# PORT_SINGLE.net
KiCad netlist of a schematic drawn in Altium Designer
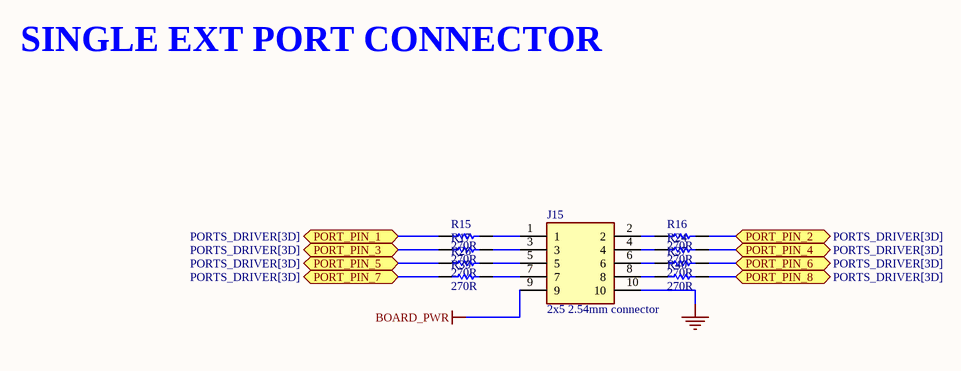
[diagram p0: PORT_SINGLE.SchDoc]

(export (version "E")
  (design (tool "Eeschema 10.0.6"))
  (components
    (comp (ref "J15")
      (value "2x5 2.54mm connector")
      (footprint "PcbLib1:SHDR10W64P254_2X5_2032X910X935P")
      (description "2x5position -  2.54x2.54mm connector")
      (fields (field (name "PARTNUMBER") "G821EU210AAL10Y"))
      (libsource (lib "Schlib1") (part "connector - 5x2 -  2.54x2.54mm"))
    )
    (comp (ref "R15")
      (value "270R")
      (footprint "RESC1005X40X25NL05T05")
      (description "Resistor - 0402 - 270R - 1% - 125mW")
      (fields (field (name "PARTNUMBER") "CRGP0402F270R"))
      (libsource (lib "Schlib1") (part "Resistor - 0402 -270R"))
    )
    (comp (ref "R16")
      (value "270R")
      (footprint "RESC1005X40X25NL05T05")
      (description "Resistor - 0402 - 270R - 1% - 125mW")
      (fields (field (name "PARTNUMBER") "CRGP0402F270R"))
      (libsource (lib "Schlib1") (part "Resistor - 0402 -270R"))
    )
    (comp (ref "R17")
      (value "270R")
      (footprint "RESC1005X40X25NL05T05")
      (description "Resistor - 0402 - 270R - 1% - 125mW")
      (fields (field (name "PARTNUMBER") "CRGP0402F270R"))
      (libsource (lib "Schlib1") (part "Resistor - 0402 -270R"))
    )
    (comp (ref "R24")
      (value "270R")
      (footprint "RESC1005X40X25NL05T05")
      (description "Resistor - 0402 - 270R - 1% - 125mW")
      (fields (field (name "PARTNUMBER") "CRGP0402F270R"))
      (libsource (lib "Schlib1") (part "Resistor - 0402 -270R"))
    )
    (comp (ref "R26")
      (value "270R")
      (footprint "RESC1005X40X25NL05T05")
      (description "Resistor - 0402 - 270R - 1% - 125mW")
      (fields (field (name "PARTNUMBER") "CRGP0402F270R"))
      (libsource (lib "Schlib1") (part "Resistor - 0402 -270R"))
    )
    (comp (ref "R37")
      (value "270R")
      (footprint "RESC1005X40X25NL05T05")
      (description "Resistor - 0402 - 270R - 1% - 125mW")
      (fields (field (name "PARTNUMBER") "CRGP0402F270R"))
      (libsource (lib "Schlib1") (part "Resistor - 0402 -270R"))
    )
    (comp (ref "R39")
      (value "270R")
      (footprint "RESC1005X40X25NL05T05")
      (description "Resistor - 0402 - 270R - 1% - 125mW")
      (fields (field (name "PARTNUMBER") "CRGP0402F270R"))
      (libsource (lib "Schlib1") (part "Resistor - 0402 -270R"))
    )
    (comp (ref "R40")
      (value "270R")
      (footprint "RESC1005X40X25NL05T05")
      (description "Resistor - 0402 - 270R - 1% - 125mW")
      (fields (field (name "PARTNUMBER") "CRGP0402F270R"))
      (libsource (lib "Schlib1") (part "Resistor - 0402 -270R"))
    )
  )
  (nets
    (net (code "1") (name "/PORT_PIN_1") (class "Default")
      (node (ref "R15") (pin "2") (pinfunction "2_2") (pintype "passive"))
    )
    (net (code "2") (name "/PORT_PIN_2") (class "Default")
      (node (ref "R16") (pin "1") (pinfunction "1_1") (pintype "passive"))
    )
    (net (code "3") (name "/PORT_PIN_3") (class "Default")
      (node (ref "R17") (pin "2") (pinfunction "2_2") (pintype "passive"))
    )
    (net (code "4") (name "/PORT_PIN_4") (class "Default")
      (node (ref "R24") (pin "1") (pinfunction "1_1") (pintype "passive"))
    )
    (net (code "5") (name "/PORT_PIN_5") (class "Default")
      (node (ref "R26") (pin "2") (pinfunction "2_2") (pintype "passive"))
    )
    (net (code "6") (name "/PORT_PIN_6") (class "Default")
      (node (ref "R37") (pin "1") (pinfunction "1_1") (pintype "passive"))
    )
    (net (code "7") (name "/PORT_PIN_7") (class "Default")
      (node (ref "R39") (pin "2") (pinfunction "2_2") (pintype "passive"))
    )
    (net (code "8") (name "/PORT_PIN_8") (class "Default")
      (node (ref "R40") (pin "1") (pinfunction "1_1") (pintype "passive"))
    )
    (net (code "9") (name "BOARD_PWR") (class "Default")
      (node (ref "J15") (pin "9") (pinfunction "9_9") (pintype "passive"))
    )
    (net (code "10") (name "GND") (class "Default")
      (node (ref "J15") (pin "10") (pinfunction "10_10") (pintype "passive"))
    )
    (net (code "11") (name "Net-(J15-Pad1)") (class "Default")
      (node (ref "J15") (pin "1") (pinfunction "1_1") (pintype "passive"))
      (node (ref "R15") (pin "1") (pinfunction "1_1") (pintype "passive"))
    )
    (net (code "12") (name "Net-(J15-Pad2)") (class "Default")
      (node (ref "J15") (pin "2") (pinfunction "2_2") (pintype "passive"))
      (node (ref "R16") (pin "2") (pinfunction "2_2") (pintype "passive"))
    )
    (net (code "13") (name "Net-(J15-Pad3)") (class "Default")
      (node (ref "J15") (pin "3") (pinfunction "3_3") (pintype "passive"))
      (node (ref "R17") (pin "1") (pinfunction "1_1") (pintype "passive"))
    )
    (net (code "14") (name "Net-(J15-Pad4)") (class "Default")
      (node (ref "J15") (pin "4") (pinfunction "4_4") (pintype "passive"))
      (node (ref "R24") (pin "2") (pinfunction "2_2") (pintype "passive"))
    )
    (net (code "15") (name "Net-(J15-Pad5)") (class "Default")
      (node (ref "J15") (pin "5") (pinfunction "5_5") (pintype "passive"))
      (node (ref "R26") (pin "1") (pinfunction "1_1") (pintype "passive"))
    )
    (net (code "16") (name "Net-(J15-Pad6)") (class "Default")
      (node (ref "J15") (pin "6") (pinfunction "6_6") (pintype "passive"))
      (node (ref "R37") (pin "2") (pinfunction "2_2") (pintype "passive"))
    )
    (net (code "17") (name "Net-(J15-Pad7)") (class "Default")
      (node (ref "J15") (pin "7") (pinfunction "7_7") (pintype "passive"))
      (node (ref "R39") (pin "1") (pinfunction "1_1") (pintype "passive"))
    )
    (net (code "18") (name "Net-(J15-Pad8)") (class "Default")
      (node (ref "J15") (pin "8") (pinfunction "8_8") (pintype "passive"))
      (node (ref "R40") (pin "2") (pinfunction "2_2") (pintype "passive"))
    )
  )
)
